# 3_ADSTM32-Peripheral.net
KiCad netlist of a schematic drawn in Altium Designer
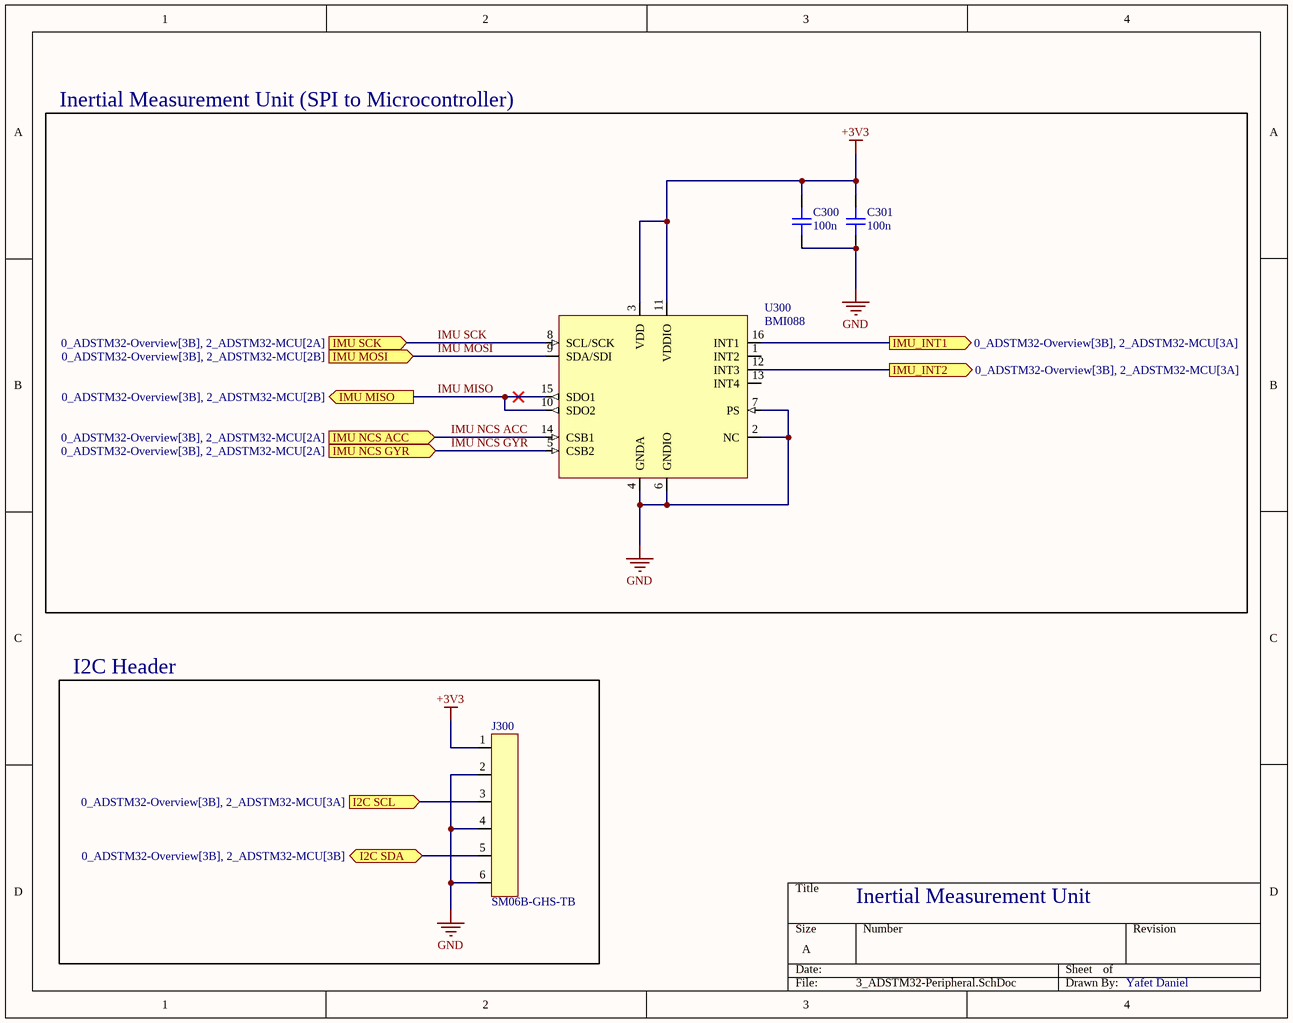
[diagram p0: 3_ADSTM32-Peripheral.SchDoc]

(export (version "E")
  (design (tool "Eeschema 10.0.6"))
  (components
    (comp (ref "C300")
      (value "100n")
      (footprint "CAP_0603")
      (description "Capacitor SMD 0603")
      (libsource (lib "Schematic-Lib-PhilsLab") (part "CAP_0603"))
    )
    (comp (ref "C301")
      (value "100n")
      (footprint "CAP_0603")
      (description "Capacitor SMD 0603")
      (libsource (lib "Schematic-Lib-PhilsLab") (part "CAP_0603"))
    )
    (comp (ref "J300")
      (value "SM06B-GHS-TB")
      (footprint "SM06B-GHS-TB")
      (description "Header Connector 6 Position 1.25MM Pitch SMD Horizontal JST GH")
      (fields (field (name "MANUFACTURER") "JST"))
      (libsource (lib "Schematic-Lib-PhilsLab") (part "SM06B-GHS-TB"))
    )
    (comp (ref "U300")
      (value "BMI088")
      (footprint "BMI088")
      (description "Inertial Measurement Unit IMU 6-Axis LGA")
      (fields (field (name "MANUFACTURER") "Bosch"))
      (libsource (lib "Schematic-Lib-PhilsLab") (part "BMI088"))
    )
  )
  (nets
    (net (code "1") (name "+3V3") (class "Default")
      (node (ref "C300") (pin "2") (pinfunction "2_2") (pintype "passive"))
      (node (ref "C301") (pin "2") (pinfunction "2_2") (pintype "passive"))
      (node (ref "J300") (pin "1") (pinfunction "1_1") (pintype "passive"))
      (node (ref "U300") (pin "11") (pinfunction "VDDIO_11") (pintype "power_in"))
      (node (ref "U300") (pin "3") (pinfunction "VDD_3") (pintype "power_in"))
    )
    (net (code "2") (name "/I2C SCL") (class "Default")
      (node (ref "J300") (pin "3") (pinfunction "3_3") (pintype "passive"))
    )
    (net (code "3") (name "/I2C SDA") (class "Default")
      (node (ref "J300") (pin "5") (pinfunction "5_5") (pintype "passive"))
    )
    (net (code "4") (name "/IMU MISO") (class "Default")
      (node (ref "U300") (pin "10") (pinfunction "SDO2_10") (pintype "output"))
      (node (ref "U300") (pin "15") (pinfunction "SDO1_15") (pintype "output"))
    )
    (net (code "5") (name "/IMU MOSI") (class "Default")
      (node (ref "U300") (pin "9") (pinfunction "SDA/SDI_9") (pintype "bidirectional"))
    )
    (net (code "6") (name "/IMU NCS ACC") (class "Default")
      (node (ref "U300") (pin "14") (pinfunction "CSB1_14") (pintype "input"))
    )
    (net (code "7") (name "/IMU NCS GYR") (class "Default")
      (node (ref "U300") (pin "5") (pinfunction "CSB2_5") (pintype "input"))
    )
    (net (code "8") (name "/IMU SCK") (class "Default")
      (node (ref "U300") (pin "8") (pinfunction "SCL/SCK_8") (pintype "input"))
    )
    (net (code "9") (name "/IMU_INT1") (class "Default")
      (node (ref "U300") (pin "16") (pinfunction "INT1_16") (pintype "bidirectional"))
    )
    (net (code "10") (name "/IMU_INT2") (class "Default")
      (node (ref "U300") (pin "12") (pinfunction "INT3_12") (pintype "bidirectional"))
    )
    (net (code "11") (name "GND") (class "Default")
      (node (ref "C300") (pin "1") (pinfunction "1_1") (pintype "passive"))
      (node (ref "C301") (pin "1") (pinfunction "1_1") (pintype "passive"))
      (node (ref "J300") (pin "2") (pinfunction "2_2") (pintype "passive"))
      (node (ref "J300") (pin "4") (pinfunction "4_4") (pintype "passive"))
      (node (ref "J300") (pin "6") (pinfunction "6_6") (pintype "passive"))
      (node (ref "U300") (pin "2") (pinfunction "NC_2") (pintype "passive"))
      (node (ref "U300") (pin "4") (pinfunction "GNDA_4") (pintype "power_in"))
      (node (ref "U300") (pin "6") (pinfunction "GNDIO_6") (pintype "power_in"))
      (node (ref "U300") (pin "7") (pinfunction "PS_7") (pintype "input"))
    )
    (net (code "12") (name "unconnected-(U300-INT2-Pad1)") (class "Default")
      (node (ref "U300") (pin "1") (pinfunction "INT2_1") (pintype "bidirectional"))
    )
    (net (code "13") (name "unconnected-(U300-INT4-Pad13)") (class "Default")
      (node (ref "U300") (pin "13") (pinfunction "INT4_13") (pintype "bidirectional"))
    )
  )
)
